# I2C_Expansion_Board_v0_1A.net
KiCad netlist of a schematic drawn in EAGLE
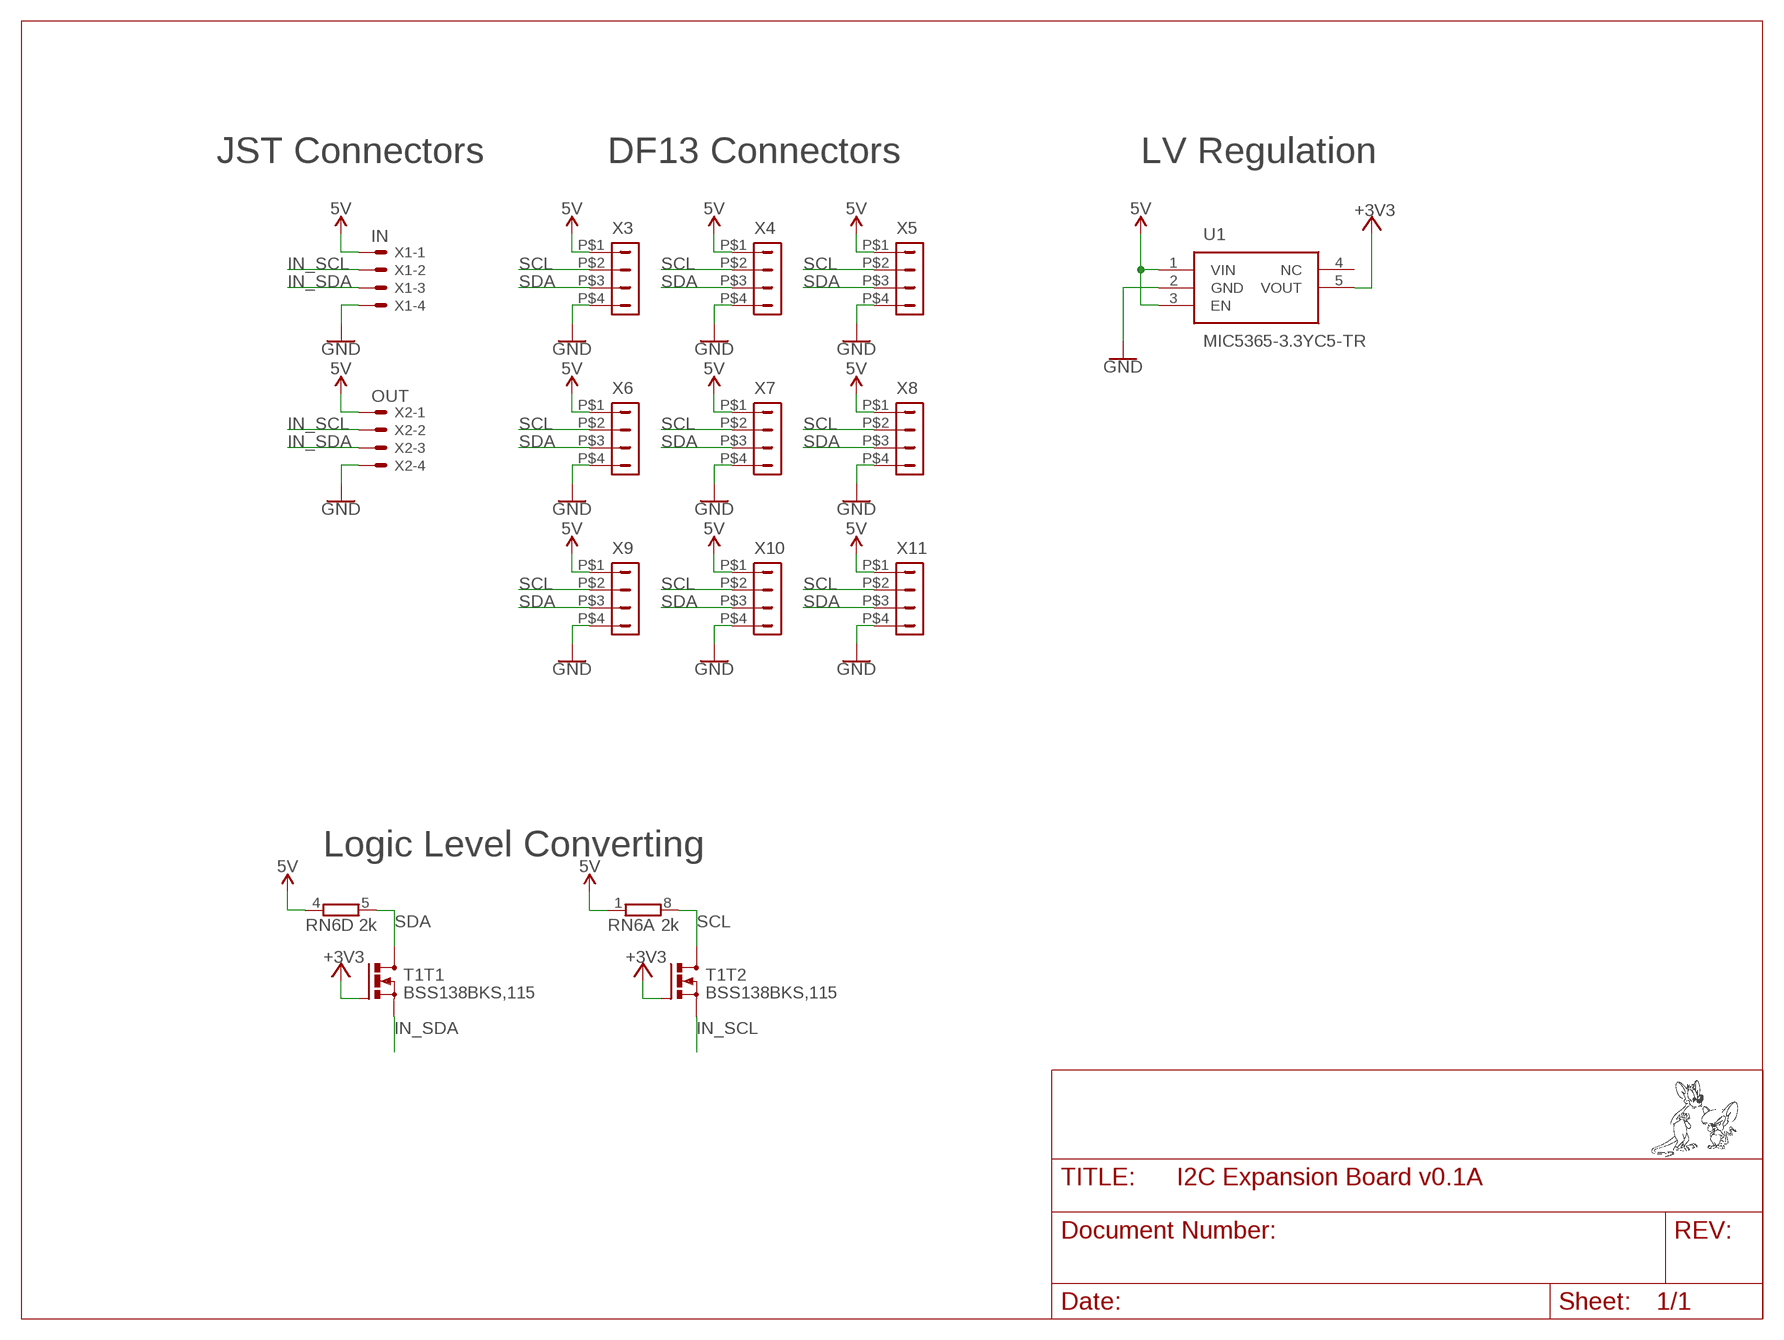
[diagram p0: schematic, sheet 1]

(export (version "E")
  (design (tool "Eeschema 10.0.6"))
  (components
    (comp (ref "RN6")
      (value "2k")
      (footprint "eagle-import:EXB28V")
      (libsource (lib "eagle-import") (part "4R-NEXB28V"))
    )
    (comp (ref "T1")
      (value "BSS138BKS,115")
      (footprint "eagle-import:SOT363")
      (fields (field (name "MF") "Nexperia USA"))
      (libsource (lib "eagle-import") (part "BSS138BKS,115"))
    )
    (comp (ref "U1")
      (value "MIC5365-3.3YC5-TR")
      (footprint "eagle-import:SOT65P210X110-5N")
      (fields
        (field (name "MOUSER_PART_NUMBER") "998-MIC5365-3.3YC5TR")
        (field (name "RS_PART_NUMBER") "1773258P")
      )
      (libsource (lib "eagle-import") (part "MIC5365-3.3YC5-TR"))
    )
    (comp (ref "X1")
      (value "IN")
      (footprint "eagle-import:JST-XH-04-PACKAGE-LONG-PAD")
      (libsource (lib "eagle-import") (part "JST-XH-04-PIN-LONG-PAD"))
    )
    (comp (ref "X2")
      (value "OUT")
      (footprint "eagle-import:JST-XH-04-PACKAGE-LONG-PAD")
      (libsource (lib "eagle-import") (part "JST-XH-04-PIN-LONG-PAD"))
    )
    (comp (ref "X3")
      (value "DF13-4P-1.25DSA")
      (footprint "eagle-import:DF13-4P-1.25DSA")
      (libsource (lib "eagle-import") (part "DF13-4P-1.25DSA"))
    )
    (comp (ref "X4")
      (value "DF13-4P-1.25DSA")
      (footprint "eagle-import:DF13-4P-1.25DSA")
      (libsource (lib "eagle-import") (part "DF13-4P-1.25DSA"))
    )
    (comp (ref "X5")
      (value "DF13-4P-1.25DSA")
      (footprint "eagle-import:DF13-4P-1.25DSA")
      (libsource (lib "eagle-import") (part "DF13-4P-1.25DSA"))
    )
    (comp (ref "X6")
      (value "DF13-4P-1.25DSA")
      (footprint "eagle-import:DF13-4P-1.25DSA")
      (libsource (lib "eagle-import") (part "DF13-4P-1.25DSA"))
    )
    (comp (ref "X7")
      (value "DF13-4P-1.25DSA")
      (footprint "eagle-import:DF13-4P-1.25DSA")
      (libsource (lib "eagle-import") (part "DF13-4P-1.25DSA"))
    )
    (comp (ref "X8")
      (value "DF13-4P-1.25DSA")
      (footprint "eagle-import:DF13-4P-1.25DSA")
      (libsource (lib "eagle-import") (part "DF13-4P-1.25DSA"))
    )
    (comp (ref "X9")
      (value "DF13-4P-1.25DSA")
      (footprint "eagle-import:DF13-4P-1.25DSA")
      (libsource (lib "eagle-import") (part "DF13-4P-1.25DSA"))
    )
    (comp (ref "X10")
      (value "DF13-4P-1.25DSA")
      (footprint "eagle-import:DF13-4P-1.25DSA")
      (libsource (lib "eagle-import") (part "DF13-4P-1.25DSA"))
    )
    (comp (ref "X11")
      (value "DF13-4P-1.25DSA")
      (footprint "eagle-import:DF13-4P-1.25DSA")
      (libsource (lib "eagle-import") (part "DF13-4P-1.25DSA"))
    )
  )
  (nets
    (net (code "1") (name "+3V3") (class "Default")
      (node (ref "T1") (pin "2") (pinfunction "G_2") (pintype "passive"))
      (node (ref "T1") (pin "5") (pinfunction "G_5") (pintype "passive"))
      (node (ref "U1") (pin "5") (pinfunction "VOUT_5") (pintype "output"))
    )
    (net (code "2") (name "/IN_SCL") (class "Default")
      (node (ref "T1") (pin "4") (pinfunction "S_4") (pintype "passive"))
      (node (ref "X1") (pin "2") (pinfunction "S_2") (pintype "passive"))
      (node (ref "X2") (pin "2") (pinfunction "S_2") (pintype "passive"))
    )
    (net (code "3") (name "/IN_SDA") (class "Default")
      (node (ref "T1") (pin "1") (pinfunction "S_1") (pintype "passive"))
      (node (ref "X1") (pin "3") (pinfunction "S_3") (pintype "passive"))
      (node (ref "X2") (pin "3") (pinfunction "S_3") (pintype "passive"))
    )
    (net (code "4") (name "/SCL") (class "Default")
      (node (ref "RN6") (pin "8") (pinfunction "2_8") (pintype "passive"))
      (node (ref "T1") (pin "3") (pinfunction "D_3") (pintype "passive"))
      (node (ref "X10") (pin "P$2") (pinfunction "2_P$2") (pintype "passive"))
      (node (ref "X11") (pin "P$2") (pinfunction "2_P$2") (pintype "passive"))
      (node (ref "X3") (pin "P$2") (pinfunction "2_P$2") (pintype "passive"))
      (node (ref "X4") (pin "P$2") (pinfunction "2_P$2") (pintype "passive"))
      (node (ref "X5") (pin "P$2") (pinfunction "2_P$2") (pintype "passive"))
      (node (ref "X6") (pin "P$2") (pinfunction "2_P$2") (pintype "passive"))
      (node (ref "X7") (pin "P$2") (pinfunction "2_P$2") (pintype "passive"))
      (node (ref "X8") (pin "P$2") (pinfunction "2_P$2") (pintype "passive"))
      (node (ref "X9") (pin "P$2") (pinfunction "2_P$2") (pintype "passive"))
    )
    (net (code "5") (name "/SDA") (class "Default")
      (node (ref "RN6") (pin "5") (pinfunction "2_5") (pintype "passive"))
      (node (ref "T1") (pin "6") (pinfunction "D_6") (pintype "passive"))
      (node (ref "X10") (pin "P$3") (pinfunction "3_P$3") (pintype "passive"))
      (node (ref "X11") (pin "P$3") (pinfunction "3_P$3") (pintype "passive"))
      (node (ref "X3") (pin "P$3") (pinfunction "3_P$3") (pintype "passive"))
      (node (ref "X4") (pin "P$3") (pinfunction "3_P$3") (pintype "passive"))
      (node (ref "X5") (pin "P$3") (pinfunction "3_P$3") (pintype "passive"))
      (node (ref "X6") (pin "P$3") (pinfunction "3_P$3") (pintype "passive"))
      (node (ref "X7") (pin "P$3") (pinfunction "3_P$3") (pintype "passive"))
      (node (ref "X8") (pin "P$3") (pinfunction "3_P$3") (pintype "passive"))
      (node (ref "X9") (pin "P$3") (pinfunction "3_P$3") (pintype "passive"))
    )
    (net (code "6") (name "5V") (class "Default")
      (node (ref "RN6") (pin "1") (pinfunction "1_1") (pintype "passive"))
      (node (ref "RN6") (pin "4") (pinfunction "1_4") (pintype "passive"))
      (node (ref "U1") (pin "1") (pinfunction "VIN_1") (pintype "power_in"))
      (node (ref "U1") (pin "3") (pinfunction "EN_3") (pintype "input"))
      (node (ref "X1") (pin "1") (pinfunction "S_1") (pintype "passive"))
      (node (ref "X10") (pin "P$1") (pinfunction "1_P$1") (pintype "passive"))
      (node (ref "X11") (pin "P$1") (pinfunction "1_P$1") (pintype "passive"))
      (node (ref "X2") (pin "1") (pinfunction "S_1") (pintype "passive"))
      (node (ref "X3") (pin "P$1") (pinfunction "1_P$1") (pintype "passive"))
      (node (ref "X4") (pin "P$1") (pinfunction "1_P$1") (pintype "passive"))
      (node (ref "X5") (pin "P$1") (pinfunction "1_P$1") (pintype "passive"))
      (node (ref "X6") (pin "P$1") (pinfunction "1_P$1") (pintype "passive"))
      (node (ref "X7") (pin "P$1") (pinfunction "1_P$1") (pintype "passive"))
      (node (ref "X8") (pin "P$1") (pinfunction "1_P$1") (pintype "passive"))
      (node (ref "X9") (pin "P$1") (pinfunction "1_P$1") (pintype "passive"))
    )
    (net (code "7") (name "GND") (class "Default")
      (node (ref "U1") (pin "2") (pinfunction "GND_2") (pintype "power_in"))
      (node (ref "X1") (pin "4") (pinfunction "S_4") (pintype "passive"))
      (node (ref "X10") (pin "P$4") (pinfunction "4_P$4") (pintype "passive"))
      (node (ref "X11") (pin "P$4") (pinfunction "4_P$4") (pintype "passive"))
      (node (ref "X2") (pin "4") (pinfunction "S_4") (pintype "passive"))
      (node (ref "X3") (pin "P$4") (pinfunction "4_P$4") (pintype "passive"))
      (node (ref "X4") (pin "P$4") (pinfunction "4_P$4") (pintype "passive"))
      (node (ref "X5") (pin "P$4") (pinfunction "4_P$4") (pintype "passive"))
      (node (ref "X6") (pin "P$4") (pinfunction "4_P$4") (pintype "passive"))
      (node (ref "X7") (pin "P$4") (pinfunction "4_P$4") (pintype "passive"))
      (node (ref "X8") (pin "P$4") (pinfunction "4_P$4") (pintype "passive"))
      (node (ref "X9") (pin "P$4") (pinfunction "4_P$4") (pintype "passive"))
    )
    (net (code "8") (name "unconnected-(U1-NC-Pad4)") (class "Default")
      (node (ref "U1") (pin "4") (pinfunction "NC_4") (pintype "no_connect"))
    )
  )
)
